# Datalogger.net
KiCad netlist of a schematic drawn in EAGLE
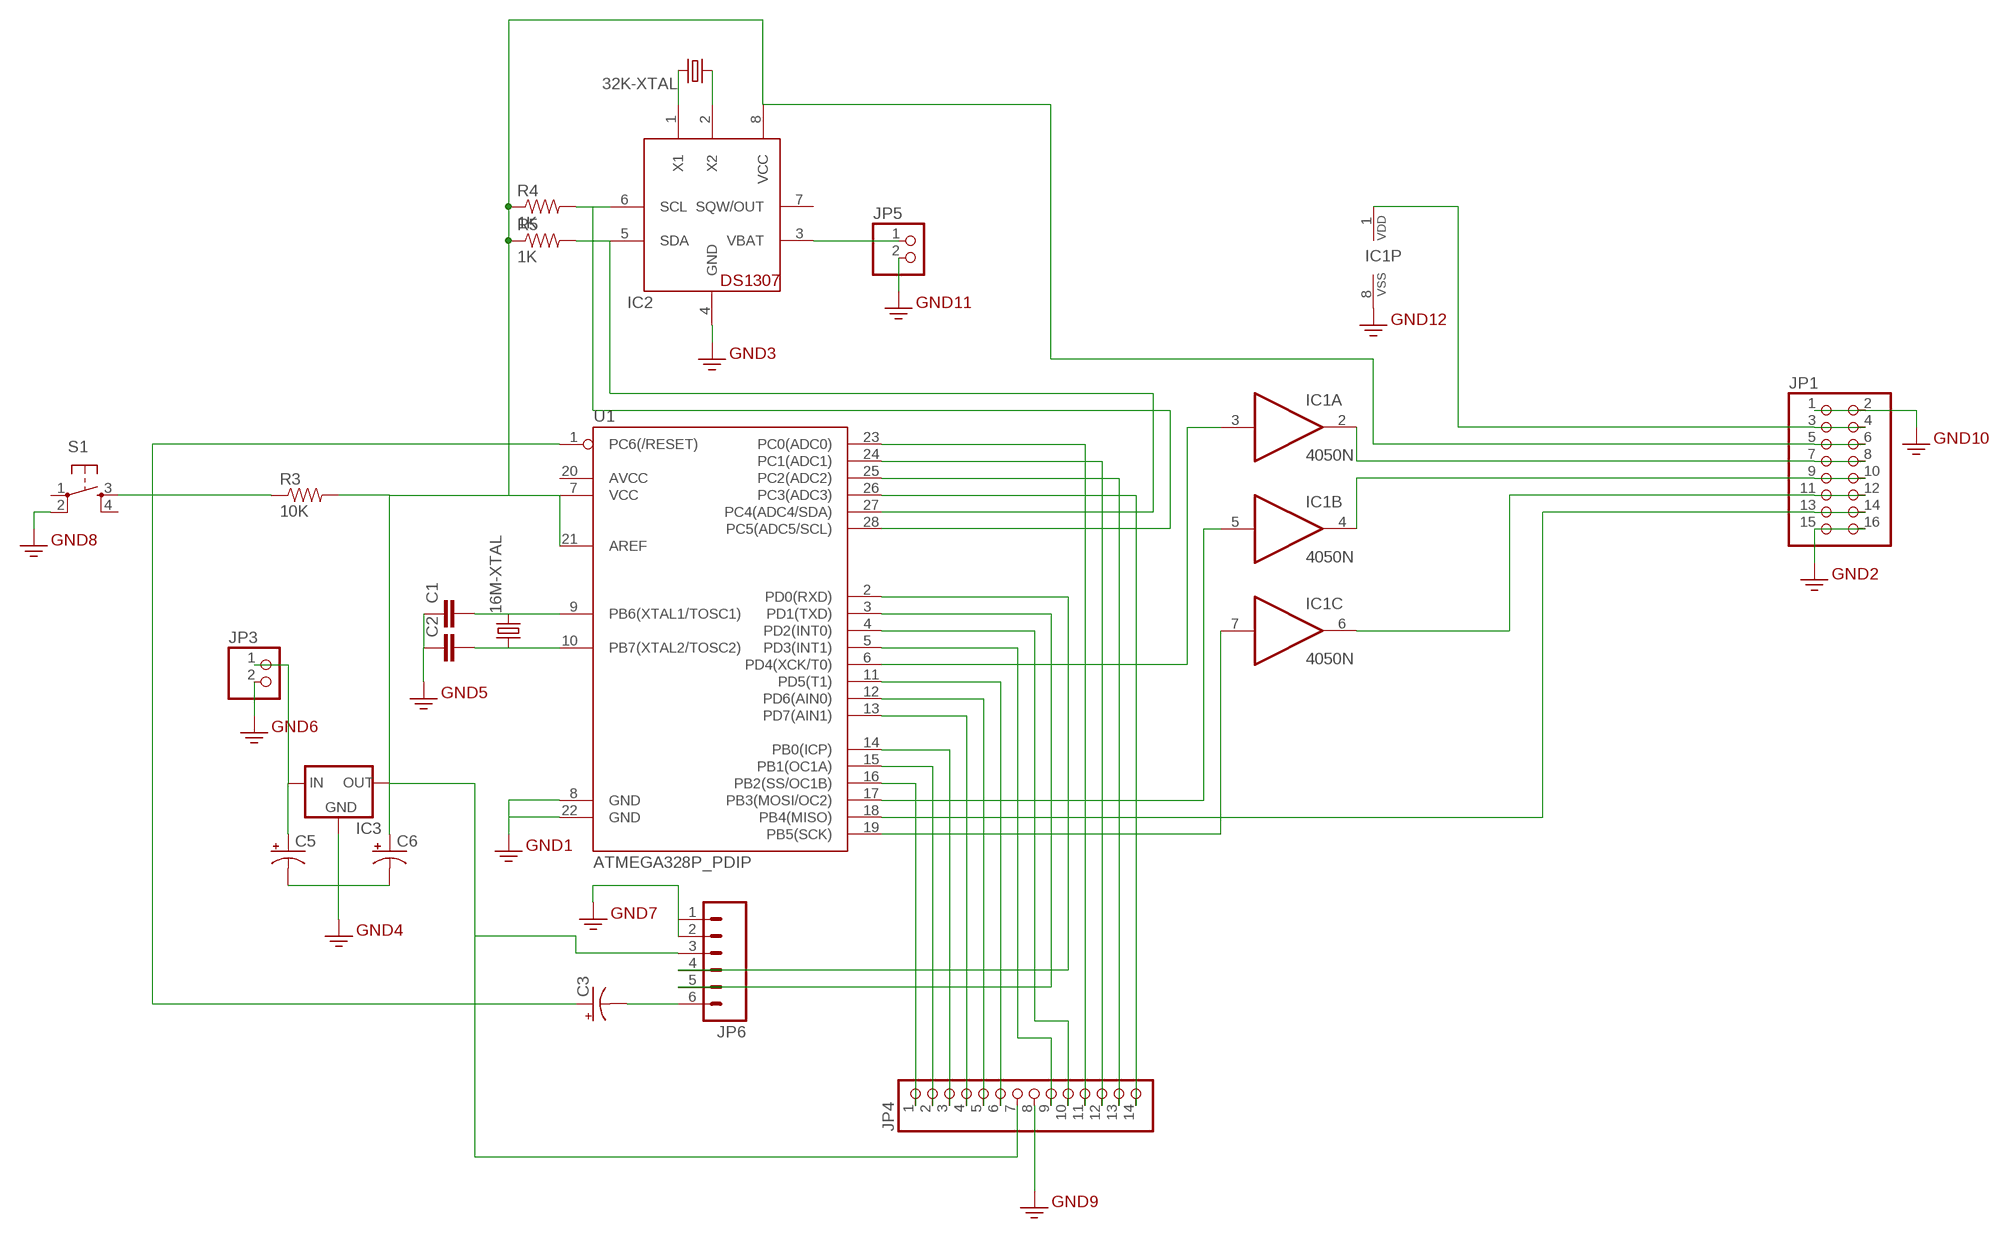
[diagram p0: schematic, sheet 1]

(export (version "E")
  (design (tool "Eeschema 10.0.6"))
  (components
    (comp (ref "16M-XTAL")
      (value "CRYSTALHC49US")
      (footprint "eagle-import:HC49US")
      (libsource (lib "eagle-import") (part "CRYSTALHC49US"))
    )
    (comp (ref "32K-XTAL")
      (value "CRYSTALTC26H_EZ")
      (footprint "eagle-import:TC26HEZ")
      (libsource (lib "eagle-import") (part "CRYSTALTC26H_EZ"))
    )
    (comp (ref "C1")
      (value "CAPKIT")
      (footprint "eagle-import:CAP-PTH-SMALL-KIT")
      (libsource (lib "eagle-import") (part "CAPKIT"))
    )
    (comp (ref "C2")
      (value "CAPKIT")
      (footprint "eagle-import:CAP-PTH-SMALL-KIT")
      (libsource (lib "eagle-import") (part "CAPKIT"))
    )
    (comp (ref "C3")
      (value "CAP_POLPTH1")
      (footprint "eagle-import:CPOL-RADIAL-100UF-25V")
      (libsource (lib "eagle-import") (part "CAP_POLPTH1"))
    )
    (comp (ref "C5")
      (value "CAP_POLPTH1")
      (footprint "eagle-import:CPOL-RADIAL-100UF-25V")
      (libsource (lib "eagle-import") (part "CAP_POLPTH1"))
    )
    (comp (ref "C6")
      (value "CAP_POLPTH1")
      (footprint "eagle-import:CPOL-RADIAL-100UF-25V")
      (libsource (lib "eagle-import") (part "CAP_POLPTH1"))
    )
    (comp (ref "IC1")
      (value "4050N")
      (footprint "eagle-import:DIL16")
      (libsource (lib "eagle-import") (part "4050N"))
    )
    (comp (ref "IC2")
      (value "DS1307")
      (footprint "eagle-import:DIL08")
      (libsource (lib "eagle-import") (part "DS1307"))
    )
    (comp (ref "IC3")
      (value "V_REG_78XX-TO-220")
      (footprint "eagle-import:TO-220-ALT")
      (libsource (lib "eagle-import") (part "V_REG_78XX-TO-220"))
    )
    (comp (ref "JP1")
      (value "PINHD-2X8")
      (footprint "eagle-import:2X08")
      (libsource (lib "eagle-import") (part "PINHD-2X8"))
    )
    (comp (ref "JP3")
      (value "PINHD-1X2")
      (footprint "eagle-import:1X02")
      (libsource (lib "eagle-import") (part "PINHD-1X2"))
    )
    (comp (ref "JP4")
      (value "PINHD-1X14")
      (footprint "eagle-import:1X14")
      (libsource (lib "eagle-import") (part "PINHD-1X14"))
    )
    (comp (ref "JP5")
      (value "PINHD-1X2")
      (footprint "eagle-import:1X02")
      (libsource (lib "eagle-import") (part "PINHD-1X2"))
    )
    (comp (ref "JP6")
      (value "M06SIP")
      (footprint "eagle-import:1X06")
      (libsource (lib "eagle-import") (part "M06SIP"))
    )
    (comp (ref "R3")
      (value "10K")
      (footprint "eagle-import:AXIAL-0.4")
      (libsource (lib "eagle-import") (part "RESISTORPTH-1/4W"))
    )
    (comp (ref "R4")
      (value "1K")
      (footprint "eagle-import:AXIAL-0.4")
      (libsource (lib "eagle-import") (part "RESISTORPTH-1/4W"))
    )
    (comp (ref "R5")
      (value "1K")
      (footprint "eagle-import:AXIAL-0.4")
      (libsource (lib "eagle-import") (part "RESISTORPTH-1/4W"))
    )
    (comp (ref "S1")
      (value "TAC_SWITCHPTH")
      (footprint "eagle-import:TACTILE-PTH")
      (libsource (lib "eagle-import") (part "TAC_SWITCHPTH"))
    )
    (comp (ref "U1")
      (value "ATMEGA328P_PDIP")
      (footprint "eagle-import:DIL28-3")
      (libsource (lib "eagle-import") (part "ATMEGA328P_PDIP"))
    )
  )
  (nets
    (net (code "1") (name "GND2") (class "Default")
      (node (ref "C1") (pin "1") (pinfunction "1_1") (pintype "passive"))
      (node (ref "C2") (pin "1") (pinfunction "1_1") (pintype "passive"))
      (node (ref "C5") (pin "2") (pinfunction "-_2") (pintype "passive"))
      (node (ref "C6") (pin "2") (pinfunction "-_2") (pintype "passive"))
      (node (ref "IC1") (pin "8") (pinfunction "VSS_8") (pintype "power_in"))
      (node (ref "IC2") (pin "4") (pinfunction "GND_4") (pintype "power_in"))
      (node (ref "IC3") (pin "GND") (pinfunction "GND_GND") (pintype "input"))
      (node (ref "JP1") (pin "1") (pinfunction "1_1") (pintype "passive"))
      (node (ref "JP1") (pin "15") (pinfunction "15_15") (pintype "passive"))
      (node (ref "JP1") (pin "16") (pinfunction "16_16") (pintype "passive"))
      (node (ref "JP1") (pin "2") (pinfunction "2_2") (pintype "passive"))
      (node (ref "JP3") (pin "2") (pinfunction "2_2") (pintype "passive"))
      (node (ref "JP4") (pin "8") (pinfunction "8_8") (pintype "passive"))
      (node (ref "JP5") (pin "2") (pinfunction "2_2") (pintype "passive"))
      (node (ref "JP6") (pin "1") (pinfunction "1_1") (pintype "passive"))
      (node (ref "JP6") (pin "2") (pinfunction "2_2") (pintype "passive"))
      (node (ref "S1") (pin "2") (pinfunction "2_2") (pintype "passive"))
      (node (ref "U1") (pin "22") (pinfunction "GND_22") (pintype "bidirectional"))
      (node (ref "U1") (pin "8") (pinfunction "GND_8") (pintype "bidirectional"))
    )
    (net (code "2") (name "Net-(C3-+)") (class "Default")
      (node (ref "C3") (pin "1") (pinfunction "+_1") (pintype "passive"))
      (node (ref "U1") (pin "1") (pinfunction "PC6(/RESET)_1") (pintype "bidirectional"))
    )
    (net (code "3") (name "Net-(C3--)") (class "Default")
      (node (ref "C3") (pin "2") (pinfunction "-_2") (pintype "passive"))
      (node (ref "JP6") (pin "6") (pinfunction "6_6") (pintype "passive"))
    )
    (net (code "4") (name "Net-(C5-+)") (class "Default")
      (node (ref "C5") (pin "1") (pinfunction "+_1") (pintype "passive"))
      (node (ref "IC3") (pin "IN") (pinfunction "IN_IN") (pintype "input"))
      (node (ref "JP3") (pin "1") (pinfunction "1_1") (pintype "passive"))
    )
    (net (code "5") (name "Net-(C6-+)") (class "Default")
      (node (ref "C6") (pin "1") (pinfunction "+_1") (pintype "passive"))
      (node (ref "IC2") (pin "8") (pinfunction "VCC_8") (pintype "power_in"))
      (node (ref "IC3") (pin "OUT") (pinfunction "OUT_OUT") (pintype "output"))
      (node (ref "JP1") (pin "5") (pinfunction "5_5") (pintype "passive"))
      (node (ref "JP1") (pin "6") (pinfunction "6_6") (pintype "passive"))
      (node (ref "JP4") (pin "7") (pinfunction "7_7") (pintype "passive"))
      (node (ref "JP6") (pin "3") (pinfunction "3_3") (pintype "passive"))
      (node (ref "R3") (pin "P$2") (pinfunction "2_P$2") (pintype "passive"))
      (node (ref "R4") (pin "P$1") (pinfunction "1_P$1") (pintype "passive"))
      (node (ref "R5") (pin "P$1") (pinfunction "1_P$1") (pintype "passive"))
      (node (ref "U1") (pin "21") (pinfunction "AREF_21") (pintype "bidirectional"))
      (node (ref "U1") (pin "7") (pinfunction "VCC_7") (pintype "bidirectional"))
    )
    (net (code "6") (name "Net-(IC1A-I)") (class "Default")
      (node (ref "IC1") (pin "3") (pinfunction "I_3") (pintype "input"))
      (node (ref "U1") (pin "6") (pinfunction "PD4(XCK/T0)_6") (pintype "bidirectional"))
    )
    (net (code "7") (name "Net-(IC1A-O)") (class "Default")
      (node (ref "IC1") (pin "2") (pinfunction "O_2") (pintype "output"))
      (node (ref "JP1") (pin "7") (pinfunction "7_7") (pintype "passive"))
      (node (ref "JP1") (pin "8") (pinfunction "8_8") (pintype "passive"))
    )
    (net (code "8") (name "Net-(IC1B-I)") (class "Default")
      (node (ref "IC1") (pin "5") (pinfunction "I_5") (pintype "input"))
      (node (ref "U1") (pin "17") (pinfunction "PB3(MOSI/OC2)_17") (pintype "bidirectional"))
    )
    (net (code "9") (name "Net-(IC1B-O)") (class "Default")
      (node (ref "IC1") (pin "4") (pinfunction "O_4") (pintype "output"))
      (node (ref "JP1") (pin "10") (pinfunction "10_10") (pintype "passive"))
      (node (ref "JP1") (pin "9") (pinfunction "9_9") (pintype "passive"))
    )
    (net (code "10") (name "Net-(IC1C-I)") (class "Default")
      (node (ref "IC1") (pin "7") (pinfunction "I_7") (pintype "input"))
      (node (ref "U1") (pin "19") (pinfunction "PB5(SCK)_19") (pintype "bidirectional"))
    )
    (net (code "11") (name "Net-(IC1C-O)") (class "Default")
      (node (ref "IC1") (pin "6") (pinfunction "O_6") (pintype "output"))
      (node (ref "JP1") (pin "11") (pinfunction "11_11") (pintype "passive"))
      (node (ref "JP1") (pin "12") (pinfunction "12_12") (pintype "passive"))
    )
    (net (code "12") (name "Net-(IC1G-VDD)") (class "Default")
      (node (ref "IC1") (pin "1") (pinfunction "VDD_1") (pintype "power_in"))
      (node (ref "JP1") (pin "3") (pinfunction "3_3") (pintype "passive"))
      (node (ref "JP1") (pin "4") (pinfunction "4_4") (pintype "passive"))
    )
    (net (code "13") (name "Net-(IC2-SCL)") (class "Default")
      (node (ref "IC2") (pin "6") (pinfunction "SCL_6") (pintype "bidirectional"))
      (node (ref "R4") (pin "P$2") (pinfunction "2_P$2") (pintype "passive"))
      (node (ref "U1") (pin "28") (pinfunction "PC5(ADC5/SCL)_28") (pintype "bidirectional"))
    )
    (net (code "14") (name "Net-(IC2-SDA)") (class "Default")
      (node (ref "IC2") (pin "5") (pinfunction "SDA_5") (pintype "bidirectional"))
      (node (ref "R5") (pin "P$2") (pinfunction "2_P$2") (pintype "passive"))
      (node (ref "U1") (pin "27") (pinfunction "PC4(ADC4/SDA)_27") (pintype "bidirectional"))
    )
    (net (code "15") (name "Net-(IC2-VBAT)") (class "Default")
      (node (ref "IC2") (pin "3") (pinfunction "VBAT_3") (pintype "power_in"))
      (node (ref "JP5") (pin "1") (pinfunction "1_1") (pintype "passive"))
    )
    (net (code "16") (name "Net-(IC2-X1)") (class "Default")
      (node (ref "32K-XTAL") (pin "2") (pinfunction "2_2") (pintype "passive"))
      (node (ref "IC2") (pin "1") (pinfunction "X1_1") (pintype "passive"))
    )
    (net (code "17") (name "Net-(IC2-X2)") (class "Default")
      (node (ref "32K-XTAL") (pin "1") (pinfunction "1_1") (pintype "passive"))
      (node (ref "IC2") (pin "2") (pinfunction "X2_2") (pintype "passive"))
    )
    (net (code "18") (name "Net-(R3-1)") (class "Default")
      (node (ref "R3") (pin "P$1") (pinfunction "1_P$1") (pintype "passive"))
      (node (ref "S1") (pin "3") (pinfunction "3_3") (pintype "passive"))
    )
    (net (code "19") (name "Net-(U1-PB0(ICP))") (class "Default")
      (node (ref "JP4") (pin "3") (pinfunction "3_3") (pintype "passive"))
      (node (ref "U1") (pin "14") (pinfunction "PB0(ICP)_14") (pintype "bidirectional"))
    )
    (net (code "20") (name "Net-(U1-PB1(OC1A))") (class "Default")
      (node (ref "JP4") (pin "2") (pinfunction "2_2") (pintype "passive"))
      (node (ref "U1") (pin "15") (pinfunction "PB1(OC1A)_15") (pintype "bidirectional"))
    )
    (net (code "21") (name "Net-(U1-PB2(SS{slash}OC1B))") (class "Default")
      (node (ref "JP4") (pin "1") (pinfunction "1_1") (pintype "passive"))
      (node (ref "U1") (pin "16") (pinfunction "PB2(SS/OC1B)_16") (pintype "bidirectional"))
    )
    (net (code "22") (name "Net-(U1-PB4(MISO))") (class "Default")
      (node (ref "JP1") (pin "13") (pinfunction "13_13") (pintype "passive"))
      (node (ref "JP1") (pin "14") (pinfunction "14_14") (pintype "passive"))
      (node (ref "U1") (pin "18") (pinfunction "PB4(MISO)_18") (pintype "bidirectional"))
    )
    (net (code "23") (name "Net-(U1-PB6(XTAL1{slash}TOSC1))") (class "Default")
      (node (ref "16M-XTAL") (pin "2") (pinfunction "2_2") (pintype "passive"))
      (node (ref "C1") (pin "2") (pinfunction "2_2") (pintype "passive"))
      (node (ref "U1") (pin "9") (pinfunction "PB6(XTAL1/TOSC1)_9") (pintype "bidirectional"))
    )
    (net (code "24") (name "Net-(U1-PB7(XTAL2{slash}TOSC2))") (class "Default")
      (node (ref "16M-XTAL") (pin "1") (pinfunction "1_1") (pintype "passive"))
      (node (ref "C2") (pin "2") (pinfunction "2_2") (pintype "passive"))
      (node (ref "U1") (pin "10") (pinfunction "PB7(XTAL2/TOSC2)_10") (pintype "bidirectional"))
    )
    (net (code "25") (name "Net-(U1-PC0(ADC0))") (class "Default")
      (node (ref "JP4") (pin "11") (pinfunction "11_11") (pintype "passive"))
      (node (ref "U1") (pin "23") (pinfunction "PC0(ADC0)_23") (pintype "bidirectional"))
    )
    (net (code "26") (name "Net-(U1-PC1(ADC1))") (class "Default")
      (node (ref "JP4") (pin "12") (pinfunction "12_12") (pintype "passive"))
      (node (ref "U1") (pin "24") (pinfunction "PC1(ADC1)_24") (pintype "bidirectional"))
    )
    (net (code "27") (name "Net-(U1-PC2(ADC2))") (class "Default")
      (node (ref "JP4") (pin "13") (pinfunction "13_13") (pintype "passive"))
      (node (ref "U1") (pin "25") (pinfunction "PC2(ADC2)_25") (pintype "bidirectional"))
    )
    (net (code "28") (name "Net-(U1-PC3(ADC3))") (class "Default")
      (node (ref "JP4") (pin "14") (pinfunction "14_14") (pintype "passive"))
      (node (ref "U1") (pin "26") (pinfunction "PC3(ADC3)_26") (pintype "bidirectional"))
    )
    (net (code "29") (name "Net-(U1-PD0(RXD))") (class "Default")
      (node (ref "JP6") (pin "4") (pinfunction "4_4") (pintype "passive"))
      (node (ref "U1") (pin "2") (pinfunction "PD0(RXD)_2") (pintype "bidirectional"))
    )
    (net (code "30") (name "Net-(U1-PD1(TXD))") (class "Default")
      (node (ref "JP6") (pin "5") (pinfunction "5_5") (pintype "passive"))
      (node (ref "U1") (pin "3") (pinfunction "PD1(TXD)_3") (pintype "bidirectional"))
    )
    (net (code "31") (name "Net-(U1-PD2(INT0))") (class "Default")
      (node (ref "JP4") (pin "10") (pinfunction "10_10") (pintype "passive"))
      (node (ref "U1") (pin "4") (pinfunction "PD2(INT0)_4") (pintype "bidirectional"))
    )
    (net (code "32") (name "Net-(U1-PD3(INT1))") (class "Default")
      (node (ref "JP4") (pin "9") (pinfunction "9_9") (pintype "passive"))
      (node (ref "U1") (pin "5") (pinfunction "PD3(INT1)_5") (pintype "bidirectional"))
    )
    (net (code "33") (name "Net-(U1-PD5(T1))") (class "Default")
      (node (ref "JP4") (pin "6") (pinfunction "6_6") (pintype "passive"))
      (node (ref "U1") (pin "11") (pinfunction "PD5(T1)_11") (pintype "bidirectional"))
    )
    (net (code "34") (name "Net-(U1-PD6(AIN0))") (class "Default")
      (node (ref "JP4") (pin "5") (pinfunction "5_5") (pintype "passive"))
      (node (ref "U1") (pin "12") (pinfunction "PD6(AIN0)_12") (pintype "bidirectional"))
    )
    (net (code "35") (name "Net-(U1-PD7(AIN1))") (class "Default")
      (node (ref "JP4") (pin "4") (pinfunction "4_4") (pintype "passive"))
      (node (ref "U1") (pin "13") (pinfunction "PD7(AIN1)_13") (pintype "bidirectional"))
    )
    (net (code "36") (name "unconnected-(IC2-SQW{slash}OUT-Pad7)") (class "Default")
      (node (ref "IC2") (pin "7") (pinfunction "SQW/OUT_7") (pintype "bidirectional"))
    )
    (net (code "37") (name "unconnected-(S1-Pad1)") (class "Default")
      (node (ref "S1") (pin "1") (pinfunction "1_1") (pintype "passive"))
    )
    (net (code "38") (name "unconnected-(S1-Pad4)") (class "Default")
      (node (ref "S1") (pin "4") (pinfunction "4_4") (pintype "passive"))
    )
    (net (code "39") (name "unconnected-(U1-AVCC-Pad20)") (class "Default")
      (node (ref "U1") (pin "20") (pinfunction "AVCC_20") (pintype "bidirectional"))
    )
  )
)
